# Sche_CB.net
KiCad netlist of a schematic drawn in Altium Designer
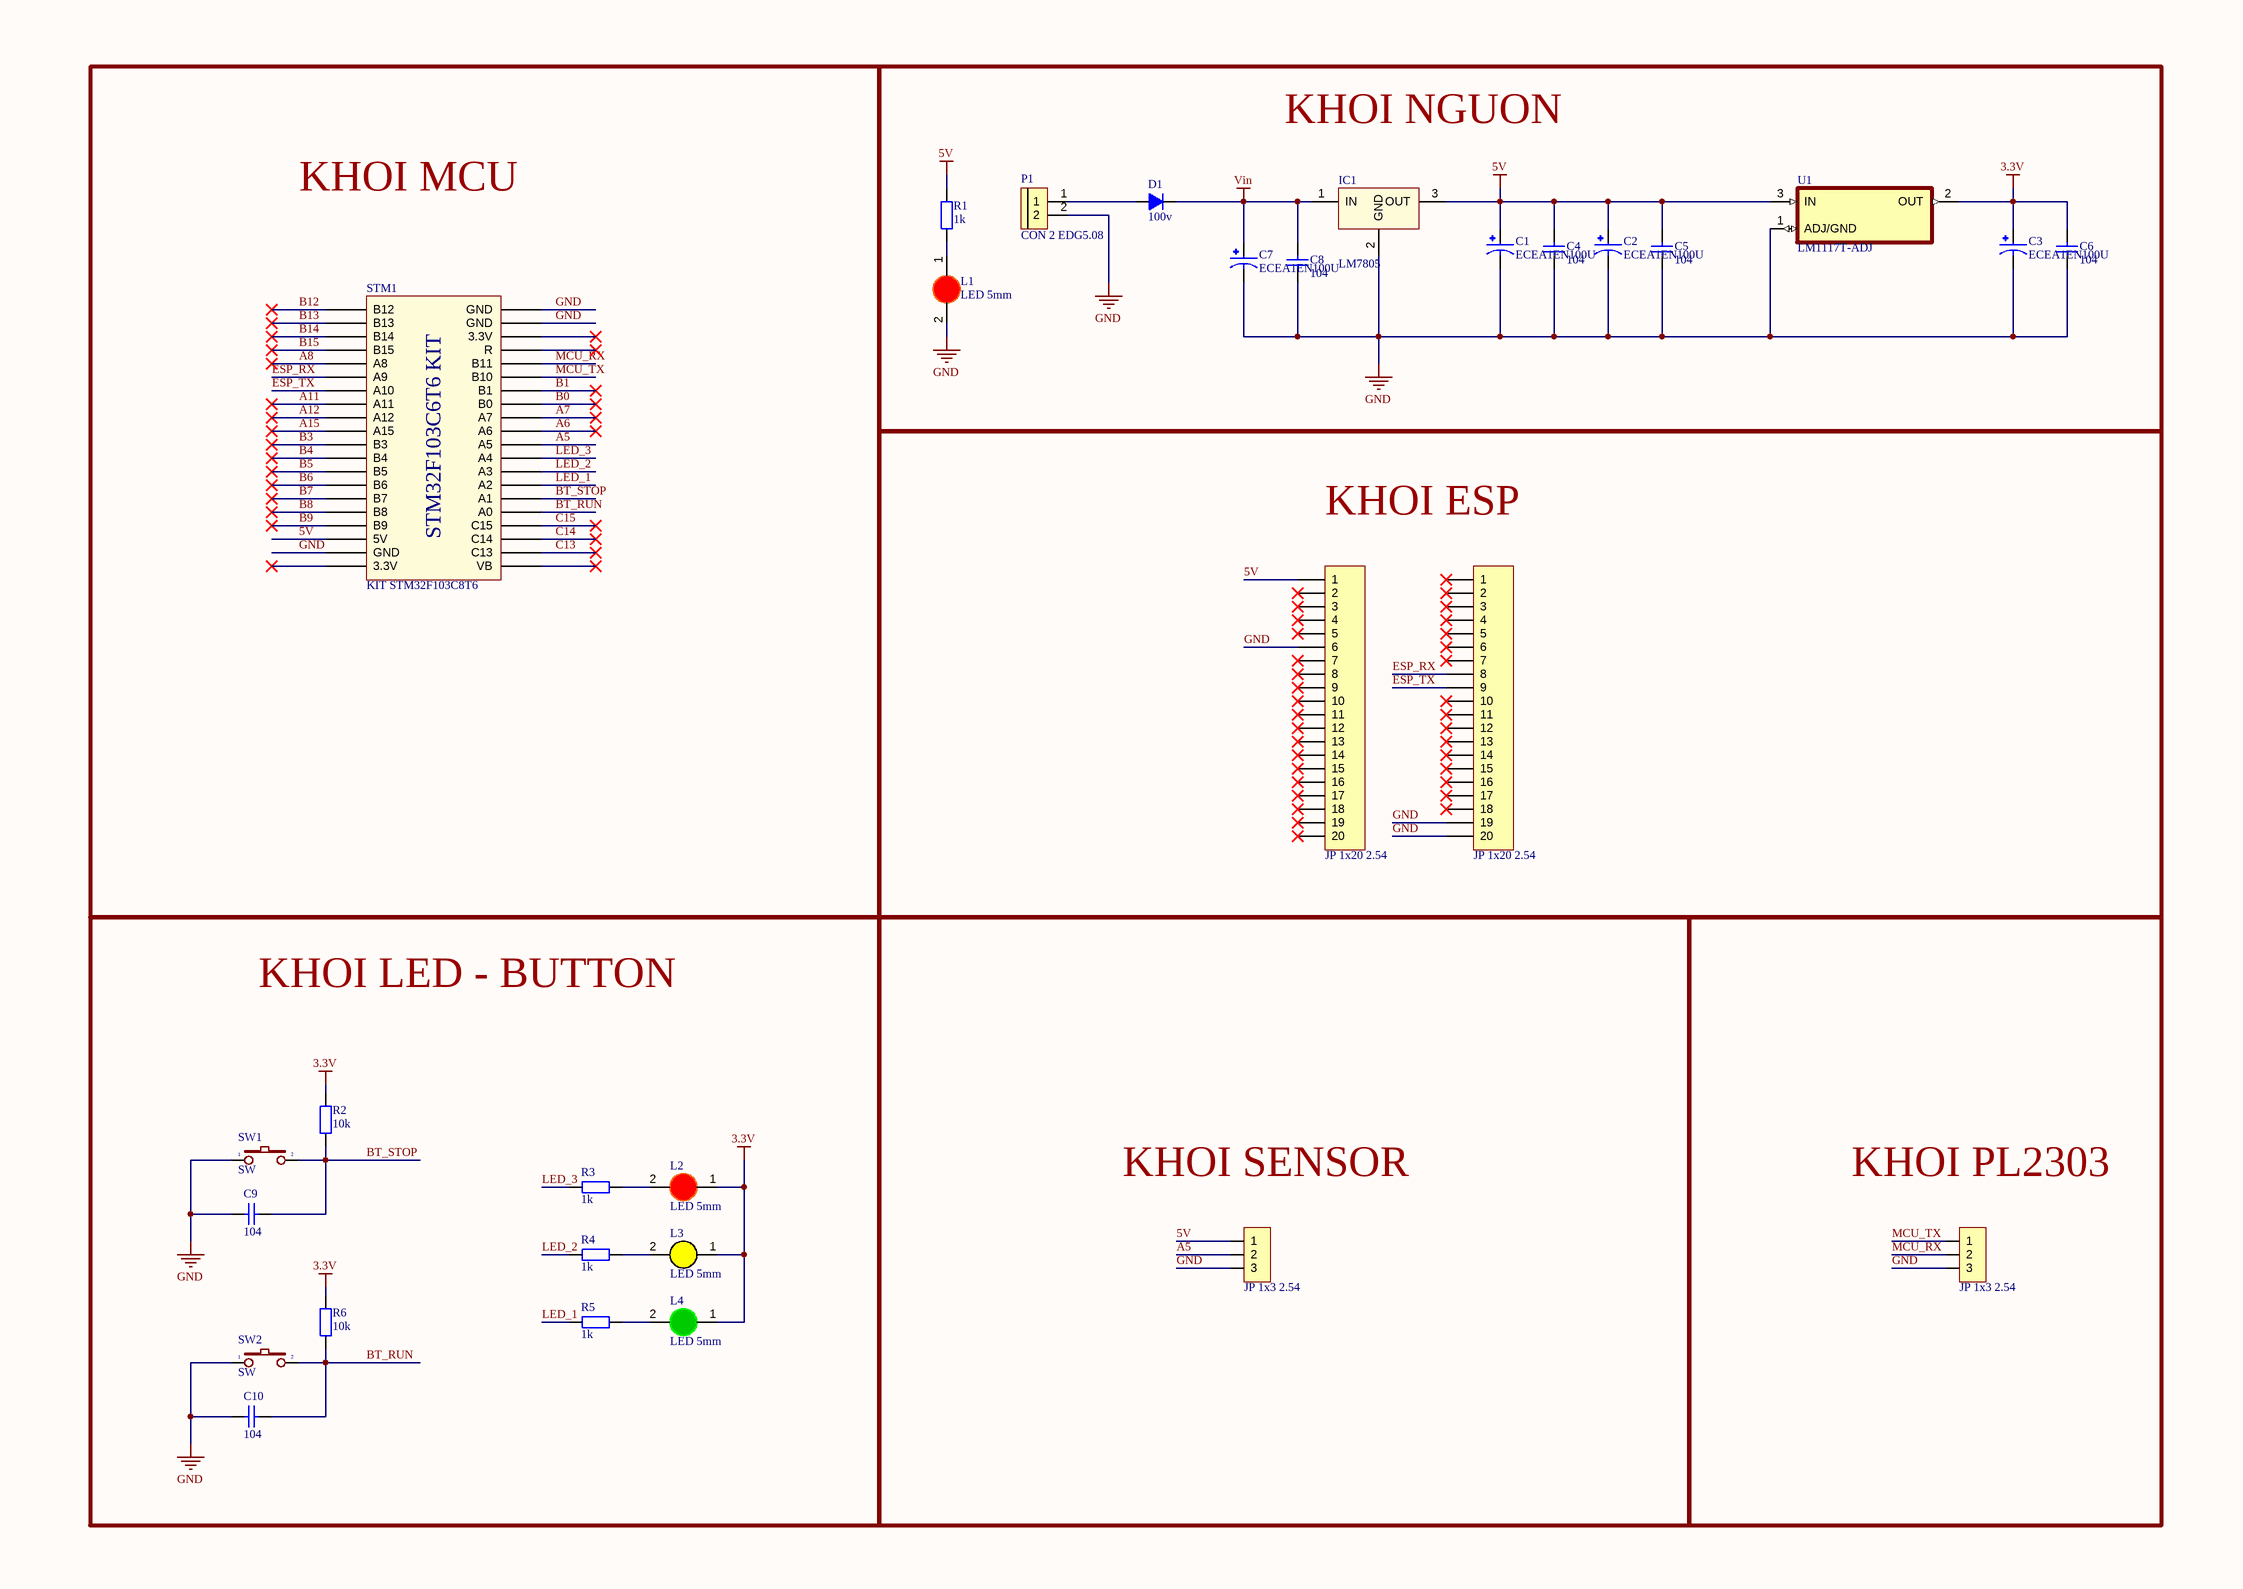
[diagram p0: Sche_CB.SchDoc]

(export (version "E")
  (design (tool "Eeschema 10.0.6"))
  (components
    (comp (ref "C1")
      (value "ECEA1EN100U")
      (footprint "CAPPRD200W50D500H1100")
      (description "10ÂµF 25V Aluminum Electrolytic Capacitors Radial, Can 2000 Hrs @ 85Â°C")
      (fields (field (name "MF") "Panasonic"))
      (libsource (lib "ECEA1EN100U") (part "ECEA1EN100U"))
    )
    (comp (ref "C2")
      (value "ECEA1EN100U")
      (footprint "CAPPRD200W50D500H1100")
      (description "10ÂµF 25V Aluminum Electrolytic Capacitors Radial, Can 2000 Hrs @ 85Â°C")
      (fields (field (name "MF") "Panasonic"))
      (libsource (lib "ECEA1EN100U") (part "ECEA1EN100U"))
    )
    (comp (ref "C3")
      (value "ECEA1EN100U")
      (footprint "CAPPRD200W50D500H1100")
      (description "10ÂµF 25V Aluminum Electrolytic Capacitors Radial, Can 2000 Hrs @ 85Â°C")
      (fields (field (name "MF") "Panasonic"))
      (libsource (lib "ECEA1EN100U") (part "ECEA1EN100U"))
    )
    (comp (ref "C4")
      (value "104")
      (footprint "tu gom")
      (description "Cắm")
      (libsource (lib "Altium_Lib_by_KhueNguyenCreator") (part "Tu gom 104 50V"))
    )
    (comp (ref "C5")
      (value "104")
      (footprint "tu gom")
      (description "Cắm")
      (libsource (lib "Altium_Lib_by_KhueNguyenCreator") (part "Tu gom 104 50V"))
    )
    (comp (ref "C6")
      (value "104")
      (footprint "tu gom")
      (description "Cắm")
      (libsource (lib "Altium_Lib_by_KhueNguyenCreator") (part "Tu gom 104 50V"))
    )
    (comp (ref "C7")
      (value "ECEA1EN100U")
      (footprint "CAPPRD200W50D500H1100")
      (description "10ÂµF 25V Aluminum Electrolytic Capacitors Radial, Can 2000 Hrs @ 85Â°C")
      (fields (field (name "MF") "Panasonic"))
      (libsource (lib "ECEA1EN100U") (part "ECEA1EN100U"))
    )
    (comp (ref "C8")
      (value "104")
      (footprint "tu gom")
      (description "Cắm")
      (libsource (lib "Altium_Lib_by_KhueNguyenCreator") (part "Tu gom 104 50V"))
    )
    (comp (ref "C9")
      (value "104")
      (footprint "tu gom")
      (description "Cắm")
      (libsource (lib "Altium_Lib_by_KhueNguyenCreator") (part "Tu gom 104 50V"))
    )
    (comp (ref "C10")
      (value "104")
      (footprint "tu gom")
      (description "Cắm")
      (libsource (lib "Altium_Lib_by_KhueNguyenCreator") (part "Tu gom 104 50V"))
    )
    (comp (ref "D1")
      (value "100v")
      (footprint "DIODE 1A")
      (description "Cắm")
      (libsource (lib "Altium_Lib_by_KhueNguyenCreator") (part "Diode 1N4007"))
    )
    (comp (ref "IC1")
      (value "LM7805")
      (footprint "QTO-220")
      (description "On ap +, from + 5 to + 24VDC")
      (libsource (lib "syhaunguyen") (part "LM78xx"))
    )
    (comp (ref "JP1")
      (value "JP 1x20 2.54")
      (footprint "JP 1x20 CT")
      (description "Cắm")
      (libsource (lib "Altium_Lib_by_KhueNguyenCreator") (part "JP 1x20 2.54 Cai Thang"))
    )
    (comp (ref "JP2")
      (value "JP 1x20 2.54")
      (footprint "JP 1x20 CT")
      (description "Cắm")
      (libsource (lib "Altium_Lib_by_KhueNguyenCreator") (part "JP 1x20 2.54 Cai Thang"))
    )
    (comp (ref "JP3")
      (value "JP 1x3 2.54")
      (footprint "JP 1x3 CT")
      (description "Cắm")
      (libsource (lib "Altium_Lib_by_KhueNguyenCreator") (part "JP 1x3 2.54 Cai Thang"))
    )
    (comp (ref "JP4")
      (value "JP 1x3 2.54")
      (footprint "JP 1x3 CT")
      (description "Cắm")
      (libsource (lib "Altium_Lib_by_KhueNguyenCreator") (part "JP 1x3 2.54 Cai Thang"))
    )
    (comp (ref "L1")
      (value "LED 5mm")
      (footprint "LED-5MM-RED")
      (description "Cắm")
      (libsource (lib "Altium_Lib_by_KhueNguyenCreator") (part "LED 5mm Do"))
    )
    (comp (ref "L2")
      (value "LED 5mm")
      (footprint "LED-5MM-RED")
      (description "Cắm")
      (libsource (lib "Altium_Lib_by_KhueNguyenCreator") (part "LED 5mm Do"))
    )
    (comp (ref "L3")
      (value "LED 5mm")
      (footprint "LED-5MM-Yellow")
      (description "Cắm")
      (libsource (lib "Altium_Lib_by_KhueNguyenCreator") (part "LED 5mm Vang"))
    )
    (comp (ref "L4")
      (value "LED 5mm")
      (footprint "LED-5MM-Green")
      (description "Cắm")
      (libsource (lib "Altium_Lib_by_KhueNguyenCreator") (part "LED 5mm Xanh La"))
    )
    (comp (ref "P1")
      (value "CON 2 EDG5.08")
      (footprint "CON 2 2EDG5.08")
      (description "Cắm")
      (libsource (lib "Altium_Lib_by_KhueNguyenCreator") (part "CON 2 EDG5.08"))
    )
    (comp (ref "R1")
      (value "1k")
      (footprint "tro vach 1/4w")
      (description "Cắm")
      (libsource (lib "Altium_Lib_by_KhueNguyenCreator") (part "Tro Vach 1/4W 5% 1k"))
    )
    (comp (ref "R2")
      (value "10k")
      (footprint "tro vach 1/4w")
      (description "Cắm")
      (libsource (lib "Altium_Lib_by_KhueNguyenCreator") (part "Tro Vach 1/4W 1% 10k"))
    )
    (comp (ref "R3")
      (value "1k")
      (footprint "tro vach 1/4w")
      (description "Cắm")
      (libsource (lib "Altium_Lib_by_KhueNguyenCreator") (part "Tro Vach 1/4W 1% 4.7k"))
    )
    (comp (ref "R4")
      (value "1k")
      (footprint "tro vach 1/4w")
      (description "Cắm")
      (libsource (lib "Altium_Lib_by_KhueNguyenCreator") (part "Tro Vach 1/4W 1% 4.7k"))
    )
    (comp (ref "R5")
      (value "1k")
      (footprint "tro vach 1/4w")
      (description "Cắm")
      (libsource (lib "Altium_Lib_by_KhueNguyenCreator") (part "Tro Vach 1/4W 1% 4.7k"))
    )
    (comp (ref "R6")
      (value "10k")
      (footprint "tro vach 1/4w")
      (description "Cắm")
      (libsource (lib "Altium_Lib_by_KhueNguyenCreator") (part "Tro Vach 1/4W 1% 10k"))
    )
    (comp (ref "STM1")
      (value "KIT STM32F103C8T6")
      (footprint "STM32F103 KIT")
      (description "KIT STM32F103C8T6 Bluepill")
      (libsource (lib "Altium_Lib_by_KhueNguyenCreator") (part "STM32f103 Bluepill"))
    )
    (comp (ref "SW1")
      (value "SW")
      (footprint "SW2")
      (description "Switch button 2 pin")
      (libsource (lib "syhaunguyen") (part "SW2"))
    )
    (comp (ref "SW2")
      (value "SW")
      (footprint "SW2")
      (description "Switch button 2 pin")
      (libsource (lib "syhaunguyen") (part "SW2"))
    )
    (comp (ref "U1")
      (value "LM1117T-ADJ")
      (footprint "TO254P1054X470X1955-3")
      (description "800-mA 15-V linear voltage regulator")
      (fields (field (name "MF") "Texas Instruments") (field (name "MP") "LM1117T-ADJ/NOPB"))
      (libsource (lib "LM1117T-ADJ") (part "LM1117T-ADJ"))
    )
  )
  (nets
    (net (code "1") (name "/A5") (class "Default")
      (node (ref "JP3") (pin "2") (pinfunction "2_2") (pintype "passive"))
      (node (ref "STM1") (pin "30") (pinfunction "A5_30") (pintype "passive"))
    )
    (net (code "2") (name "/A6") (class "Default")
      (node (ref "STM1") (pin "31") (pinfunction "A6_31") (pintype "passive+no_connect"))
    )
    (net (code "3") (name "/A7") (class "Default")
      (node (ref "STM1") (pin "32") (pinfunction "A7_32") (pintype "passive+no_connect"))
    )
    (net (code "4") (name "/A8") (class "Default")
      (node (ref "STM1") (pin "5") (pinfunction "A8_5") (pintype "passive+no_connect"))
    )
    (net (code "5") (name "/A11") (class "Default")
      (node (ref "STM1") (pin "8") (pinfunction "A11_8") (pintype "passive+no_connect"))
    )
    (net (code "6") (name "/A12") (class "Default")
      (node (ref "STM1") (pin "9") (pinfunction "A12_9") (pintype "passive+no_connect"))
    )
    (net (code "7") (name "/A15") (class "Default")
      (node (ref "STM1") (pin "10") (pinfunction "A15_10") (pintype "passive+no_connect"))
    )
    (net (code "8") (name "/B0") (class "Default")
      (node (ref "STM1") (pin "33") (pinfunction "B0_33") (pintype "passive+no_connect"))
    )
    (net (code "9") (name "/B1") (class "Default")
      (node (ref "STM1") (pin "34") (pinfunction "B1_34") (pintype "passive+no_connect"))
    )
    (net (code "10") (name "/B3") (class "Default")
      (node (ref "STM1") (pin "11") (pinfunction "B3_11") (pintype "passive+no_connect"))
    )
    (net (code "11") (name "/B4") (class "Default")
      (node (ref "STM1") (pin "12") (pinfunction "B4_12") (pintype "passive+no_connect"))
    )
    (net (code "12") (name "/B5") (class "Default")
      (node (ref "STM1") (pin "13") (pinfunction "B5_13") (pintype "passive+no_connect"))
    )
    (net (code "13") (name "/B6") (class "Default")
      (node (ref "STM1") (pin "14") (pinfunction "B6_14") (pintype "passive+no_connect"))
    )
    (net (code "14") (name "/B7") (class "Default")
      (node (ref "STM1") (pin "15") (pinfunction "B7_15") (pintype "passive+no_connect"))
    )
    (net (code "15") (name "/B8") (class "Default")
      (node (ref "STM1") (pin "16") (pinfunction "B8_16") (pintype "passive+no_connect"))
    )
    (net (code "16") (name "/B9") (class "Default")
      (node (ref "STM1") (pin "17") (pinfunction "B9_17") (pintype "passive+no_connect"))
    )
    (net (code "17") (name "/B12") (class "Default")
      (node (ref "STM1") (pin "1") (pinfunction "B12_1") (pintype "passive+no_connect"))
    )
    (net (code "18") (name "/B13") (class "Default")
      (node (ref "STM1") (pin "2") (pinfunction "B13_2") (pintype "passive+no_connect"))
    )
    (net (code "19") (name "/B14") (class "Default")
      (node (ref "STM1") (pin "3") (pinfunction "B14_3") (pintype "passive+no_connect"))
    )
    (net (code "20") (name "/B15") (class "Default")
      (node (ref "STM1") (pin "4") (pinfunction "B15_4") (pintype "passive+no_connect"))
    )
    (net (code "21") (name "/BT_RUN") (class "Default")
      (node (ref "C10") (pin "1") (pinfunction "1_1") (pintype "passive"))
      (node (ref "R6") (pin "1") (pinfunction "1_1") (pintype "passive"))
      (node (ref "STM1") (pin "25") (pinfunction "A0_25") (pintype "passive"))
      (node (ref "SW2") (pin "2") (pinfunction "2_2") (pintype "passive"))
    )
    (net (code "22") (name "/BT_STOP") (class "Default")
      (node (ref "C9") (pin "1") (pinfunction "1_1") (pintype "passive"))
      (node (ref "R2") (pin "1") (pinfunction "1_1") (pintype "passive"))
      (node (ref "STM1") (pin "26") (pinfunction "A1_26") (pintype "passive"))
      (node (ref "SW1") (pin "2") (pinfunction "2_2") (pintype "passive"))
    )
    (net (code "23") (name "/C13") (class "Default")
      (node (ref "STM1") (pin "22") (pinfunction "C13_22") (pintype "passive+no_connect"))
    )
    (net (code "24") (name "/C14") (class "Default")
      (node (ref "STM1") (pin "23") (pinfunction "C14_23") (pintype "passive+no_connect"))
    )
    (net (code "25") (name "/C15") (class "Default")
      (node (ref "STM1") (pin "24") (pinfunction "C15_24") (pintype "passive+no_connect"))
    )
    (net (code "26") (name "/ESP_RX") (class "Default")
      (node (ref "JP2") (pin "8") (pinfunction "8_8") (pintype "passive"))
      (node (ref "STM1") (pin "6") (pinfunction "A9_6") (pintype "passive"))
    )
    (net (code "27") (name "/ESP_TX") (class "Default")
      (node (ref "JP2") (pin "9") (pinfunction "9_9") (pintype "passive"))
      (node (ref "STM1") (pin "7") (pinfunction "A10_7") (pintype "passive"))
    )
    (net (code "28") (name "/LED_1") (class "Default")
      (node (ref "R5") (pin "1") (pinfunction "1_1") (pintype "passive"))
      (node (ref "STM1") (pin "27") (pinfunction "A2_27") (pintype "passive"))
    )
    (net (code "29") (name "/LED_2") (class "Default")
      (node (ref "R4") (pin "1") (pinfunction "1_1") (pintype "passive"))
      (node (ref "STM1") (pin "28") (pinfunction "A3_28") (pintype "passive"))
    )
    (net (code "30") (name "/LED_3") (class "Default")
      (node (ref "R3") (pin "1") (pinfunction "1_1") (pintype "passive"))
      (node (ref "STM1") (pin "29") (pinfunction "A4_29") (pintype "passive"))
    )
    (net (code "31") (name "/MCU_RX") (class "Default")
      (node (ref "JP4") (pin "2") (pinfunction "2_2") (pintype "passive"))
      (node (ref "STM1") (pin "36") (pinfunction "B11_36") (pintype "passive"))
    )
    (net (code "32") (name "/MCU_TX") (class "Default")
      (node (ref "JP4") (pin "1") (pinfunction "1_1") (pintype "passive"))
      (node (ref "STM1") (pin "35") (pinfunction "B10_35") (pintype "passive"))
    )
    (net (code "33") (name "3.3V") (class "Default")
      (node (ref "C3") (pin "P") (pinfunction "P_P") (pintype "passive"))
      (node (ref "C6") (pin "1") (pinfunction "1_1") (pintype "passive"))
      (node (ref "L2") (pin "1") (pinfunction "A_1") (pintype "passive"))
      (node (ref "L3") (pin "1") (pinfunction "A_1") (pintype "passive"))
      (node (ref "L4") (pin "1") (pinfunction "A_1") (pintype "passive"))
      (node (ref "R2") (pin "2") (pinfunction "2_2") (pintype "passive"))
      (node (ref "R6") (pin "2") (pinfunction "2_2") (pintype "passive"))
      (node (ref "U1") (pin "2") (pinfunction "OUT_2") (pintype "output"))
    )
    (net (code "34") (name "5V") (class "Default")
      (node (ref "C1") (pin "P") (pinfunction "P_P") (pintype "passive"))
      (node (ref "C2") (pin "P") (pinfunction "P_P") (pintype "passive"))
      (node (ref "C4") (pin "1") (pinfunction "1_1") (pintype "passive"))
      (node (ref "C5") (pin "1") (pinfunction "1_1") (pintype "passive"))
      (node (ref "IC1") (pin "3") (pinfunction "OUT_3") (pintype "passive"))
      (node (ref "JP1") (pin "1") (pinfunction "1_1") (pintype "passive"))
      (node (ref "JP3") (pin "1") (pinfunction "1_1") (pintype "passive"))
      (node (ref "R1") (pin "2") (pinfunction "2_2") (pintype "passive"))
      (node (ref "STM1") (pin "18") (pinfunction "5V_18") (pintype "passive"))
      (node (ref "U1") (pin "3") (pinfunction "IN_3") (pintype "input"))
    )
    (net (code "35") (name "GND") (class "Default")
      (node (ref "C1") (pin "N") (pinfunction "N_N") (pintype "passive"))
      (node (ref "C10") (pin "2") (pinfunction "2_2") (pintype "passive"))
      (node (ref "C2") (pin "N") (pinfunction "N_N") (pintype "passive"))
      (node (ref "C3") (pin "N") (pinfunction "N_N") (pintype "passive"))
      (node (ref "C4") (pin "2") (pinfunction "2_2") (pintype "passive"))
      (node (ref "C5") (pin "2") (pinfunction "2_2") (pintype "passive"))
      (node (ref "C6") (pin "2") (pinfunction "2_2") (pintype "passive"))
      (node (ref "C7") (pin "N") (pinfunction "N_N") (pintype "passive"))
      (node (ref "C8") (pin "2") (pinfunction "2_2") (pintype "passive"))
      (node (ref "C9") (pin "2") (pinfunction "2_2") (pintype "passive"))
      (node (ref "IC1") (pin "2") (pinfunction "GND_2") (pintype "passive"))
      (node (ref "JP1") (pin "6") (pinfunction "6_6") (pintype "passive"))
      (node (ref "JP2") (pin "19") (pinfunction "19_19") (pintype "passive"))
      (node (ref "JP2") (pin "20") (pinfunction "20_20") (pintype "passive"))
      (node (ref "JP3") (pin "3") (pinfunction "3_3") (pintype "passive"))
      (node (ref "JP4") (pin "3") (pinfunction "3_3") (pintype "passive"))
      (node (ref "L1") (pin "2") (pinfunction "K_2") (pintype "passive"))
      (node (ref "P1") (pin "2") (pinfunction "2_2") (pintype "passive"))
      (node (ref "STM1") (pin "19") (pinfunction "GND_19") (pintype "passive"))
      (node (ref "STM1") (pin "39") (pinfunction "GND_39") (pintype "passive"))
      (node (ref "STM1") (pin "40") (pinfunction "GND_40") (pintype "passive"))
      (node (ref "SW1") (pin "1") (pinfunction "1_1") (pintype "passive"))
      (node (ref "SW2") (pin "1") (pinfunction "1_1") (pintype "passive"))
      (node (ref "U1") (pin "1") (pinfunction "ADJ/GND_1") (pintype "bidirectional"))
    )
    (net (code "36") (name "Net-(D1-A)") (class "Default")
      (node (ref "D1") (pin "1") (pinfunction "A_1") (pintype "passive"))
      (node (ref "P1") (pin "1") (pinfunction "1_1") (pintype "passive"))
    )
    (net (code "37") (name "Net-(L1-A)") (class "Default")
      (node (ref "L1") (pin "1") (pinfunction "A_1") (pintype "passive"))
      (node (ref "R1") (pin "1") (pinfunction "1_1") (pintype "passive"))
    )
    (net (code "38") (name "Net-(L2-K)") (class "Default")
      (node (ref "L2") (pin "2") (pinfunction "K_2") (pintype "passive"))
      (node (ref "R3") (pin "2") (pinfunction "2_2") (pintype "passive"))
    )
    (net (code "39") (name "Net-(L3-K)") (class "Default")
      (node (ref "L3") (pin "2") (pinfunction "K_2") (pintype "passive"))
      (node (ref "R4") (pin "2") (pinfunction "2_2") (pintype "passive"))
    )
    (net (code "40") (name "Net-(L4-K)") (class "Default")
      (node (ref "L4") (pin "2") (pinfunction "K_2") (pintype "passive"))
      (node (ref "R5") (pin "2") (pinfunction "2_2") (pintype "passive"))
    )
    (net (code "41") (name "Vin") (class "Default")
      (node (ref "C7") (pin "P") (pinfunction "P_P") (pintype "passive"))
      (node (ref "C8") (pin "1") (pinfunction "1_1") (pintype "passive"))
      (node (ref "D1") (pin "2") (pinfunction "K_2") (pintype "passive"))
      (node (ref "IC1") (pin "1") (pinfunction "IN_1") (pintype "passive"))
    )
    (net (code "42") (name "unconnected-(JP1-Pad2)") (class "Default")
      (node (ref "JP1") (pin "2") (pinfunction "2_2") (pintype "passive+no_connect"))
    )
    (net (code "43") (name "unconnected-(JP1-Pad3)") (class "Default")
      (node (ref "JP1") (pin "3") (pinfunction "3_3") (pintype "passive+no_connect"))
    )
    (net (code "44") (name "unconnected-(JP1-Pad4)") (class "Default")
      (node (ref "JP1") (pin "4") (pinfunction "4_4") (pintype "passive+no_connect"))
    )
    (net (code "45") (name "unconnected-(JP1-Pad5)") (class "Default")
      (node (ref "JP1") (pin "5") (pinfunction "5_5") (pintype "passive+no_connect"))
    )
    (net (code "46") (name "unconnected-(JP1-Pad7)") (class "Default")
      (node (ref "JP1") (pin "7") (pinfunction "7_7") (pintype "passive+no_connect"))
    )
    (net (code "47") (name "unconnected-(JP1-Pad8)") (class "Default")
      (node (ref "JP1") (pin "8") (pinfunction "8_8") (pintype "passive+no_connect"))
    )
    (net (code "48") (name "unconnected-(JP1-Pad9)") (class "Default")
      (node (ref "JP1") (pin "9") (pinfunction "9_9") (pintype "passive+no_connect"))
    )
    (net (code "49") (name "unconnected-(JP1-Pad10)") (class "Default")
      (node (ref "JP1") (pin "10") (pinfunction "10_10") (pintype "passive+no_connect"))
    )
    (net (code "50") (name "unconnected-(JP1-Pad11)") (class "Default")
      (node (ref "JP1") (pin "11") (pinfunction "11_11") (pintype "passive+no_connect"))
    )
    (net (code "51") (name "unconnected-(JP1-Pad12)") (class "Default")
      (node (ref "JP1") (pin "12") (pinfunction "12_12") (pintype "passive+no_connect"))
    )
    (net (code "52") (name "unconnected-(JP1-Pad13)") (class "Default")
      (node (ref "JP1") (pin "13") (pinfunction "13_13") (pintype "passive+no_connect"))
    )
    (net (code "53") (name "unconnected-(JP1-Pad14)") (class "Default")
      (node (ref "JP1") (pin "14") (pinfunction "14_14") (pintype "passive+no_connect"))
    )
    (net (code "54") (name "unconnected-(JP1-Pad15)") (class "Default")
      (node (ref "JP1") (pin "15") (pinfunction "15_15") (pintype "passive+no_connect"))
    )
    (net (code "55") (name "unconnected-(JP1-Pad16)") (class "Default")
      (node (ref "JP1") (pin "16") (pinfunction "16_16") (pintype "passive+no_connect"))
    )
    (net (code "56") (name "unconnected-(JP1-Pad17)") (class "Default")
      (node (ref "JP1") (pin "17") (pinfunction "17_17") (pintype "passive+no_connect"))
    )
    (net (code "57") (name "unconnected-(JP1-Pad18)") (class "Default")
      (node (ref "JP1") (pin "18") (pinfunction "18_18") (pintype "passive+no_connect"))
    )
    (net (code "58") (name "unconnected-(JP1-Pad19)") (class "Default")
      (node (ref "JP1") (pin "19") (pinfunction "19_19") (pintype "passive+no_connect"))
    )
    (net (code "59") (name "unconnected-(JP1-Pad20)") (class "Default")
      (node (ref "JP1") (pin "20") (pinfunction "20_20") (pintype "passive+no_connect"))
    )
    (net (code "60") (name "unconnected-(JP2-Pad1)") (class "Default")
      (node (ref "JP2") (pin "1") (pinfunction "1_1") (pintype "passive+no_connect"))
    )
    (net (code "61") (name "unconnected-(JP2-Pad2)") (class "Default")
      (node (ref "JP2") (pin "2") (pinfunction "2_2") (pintype "passive+no_connect"))
    )
    (net (code "62") (name "unconnected-(JP2-Pad3)") (class "Default")
      (node (ref "JP2") (pin "3") (pinfunction "3_3") (pintype "passive+no_connect"))
    )
    (net (code "63") (name "unconnected-(JP2-Pad4)") (class "Default")
      (node (ref "JP2") (pin "4") (pinfunction "4_4") (pintype "passive+no_connect"))
    )
    (net (code "64") (name "unconnected-(JP2-Pad5)") (class "Default")
      (node (ref "JP2") (pin "5") (pinfunction "5_5") (pintype "passive+no_connect"))
    )
    (net (code "65") (name "unconnected-(JP2-Pad6)") (class "Default")
      (node (ref "JP2") (pin "6") (pinfunction "6_6") (pintype "passive+no_connect"))
    )
    (net (code "66") (name "unconnected-(JP2-Pad7)") (class "Default")
      (node (ref "JP2") (pin "7") (pinfunction "7_7") (pintype "passive+no_connect"))
    )
    (net (code "67") (name "unconnected-(JP2-Pad10)") (class "Default")
      (node (ref "JP2") (pin "10") (pinfunction "10_10") (pintype "passive+no_connect"))
    )
    (net (code "68") (name "unconnected-(JP2-Pad11)") (class "Default")
      (node (ref "JP2") (pin "11") (pinfunction "11_11") (pintype "passive+no_connect"))
    )
    (net (code "69") (name "unconnected-(JP2-Pad12)") (class "Default")
      (node (ref "JP2") (pin "12") (pinfunction "12_12") (pintype "passive+no_connect"))
    )
    (net (code "70") (name "unconnected-(JP2-Pad13)") (class "Default")
      (node (ref "JP2") (pin "13") (pinfunction "13_13") (pintype "passive+no_connect"))
    )
    (net (code "71") (name "unconnected-(JP2-Pad14)") (class "Default")
      (node (ref "JP2") (pin "14") (pinfunction "14_14") (pintype "passive+no_connect"))
    )
    (net (code "72") (name "unconnected-(JP2-Pad15)") (class "Default")
      (node (ref "JP2") (pin "15") (pinfunction "15_15") (pintype "passive+no_connect"))
    )
    (net (code "73") (name "unconnected-(JP2-Pad16)") (class "Default")
      (node (ref "JP2") (pin "16") (pinfunction "16_16") (pintype "passive+no_connect"))
    )
    (net (code "74") (name "unconnected-(JP2-Pad17)") (class "Default")
      (node (ref "JP2") (pin "17") (pinfunction "17_17") (pintype "passive+no_connect"))
    )
    (net (code "75") (name "unconnected-(JP2-Pad18)") (class "Default")
      (node (ref "JP2") (pin "18") (pinfunction "18_18") (pintype "passive+no_connect"))
    )
    (net (code "76") (name "unconnected-(STM1-3.3V-Pad20)") (class "Default")
      (node (ref "STM1") (pin "20") (pinfunction "3.3V_20") (pintype "passive+no_connect"))
    )
    (net (code "77") (name "unconnected-(STM1-3.3V-Pad38)") (class "Default")
      (node (ref "STM1") (pin "38") (pinfunction "3.3V_38") (pintype "passive+no_connect"))
    )
    (net (code "78") (name "unconnected-(STM1-R-Pad37)") (class "Default")
      (node (ref "STM1") (pin "37") (pinfunction "R_37") (pintype "passive+no_connect"))
    )
    (net (code "79") (name "unconnected-(STM1-VB-Pad21)") (class "Default")
      (node (ref "STM1") (pin "21") (pinfunction "VB_21") (pintype "passive+no_connect"))
    )
  )
)
